# PCB10_1_PRABHU.net
KiCad netlist of a schematic drawn in EasyEDA
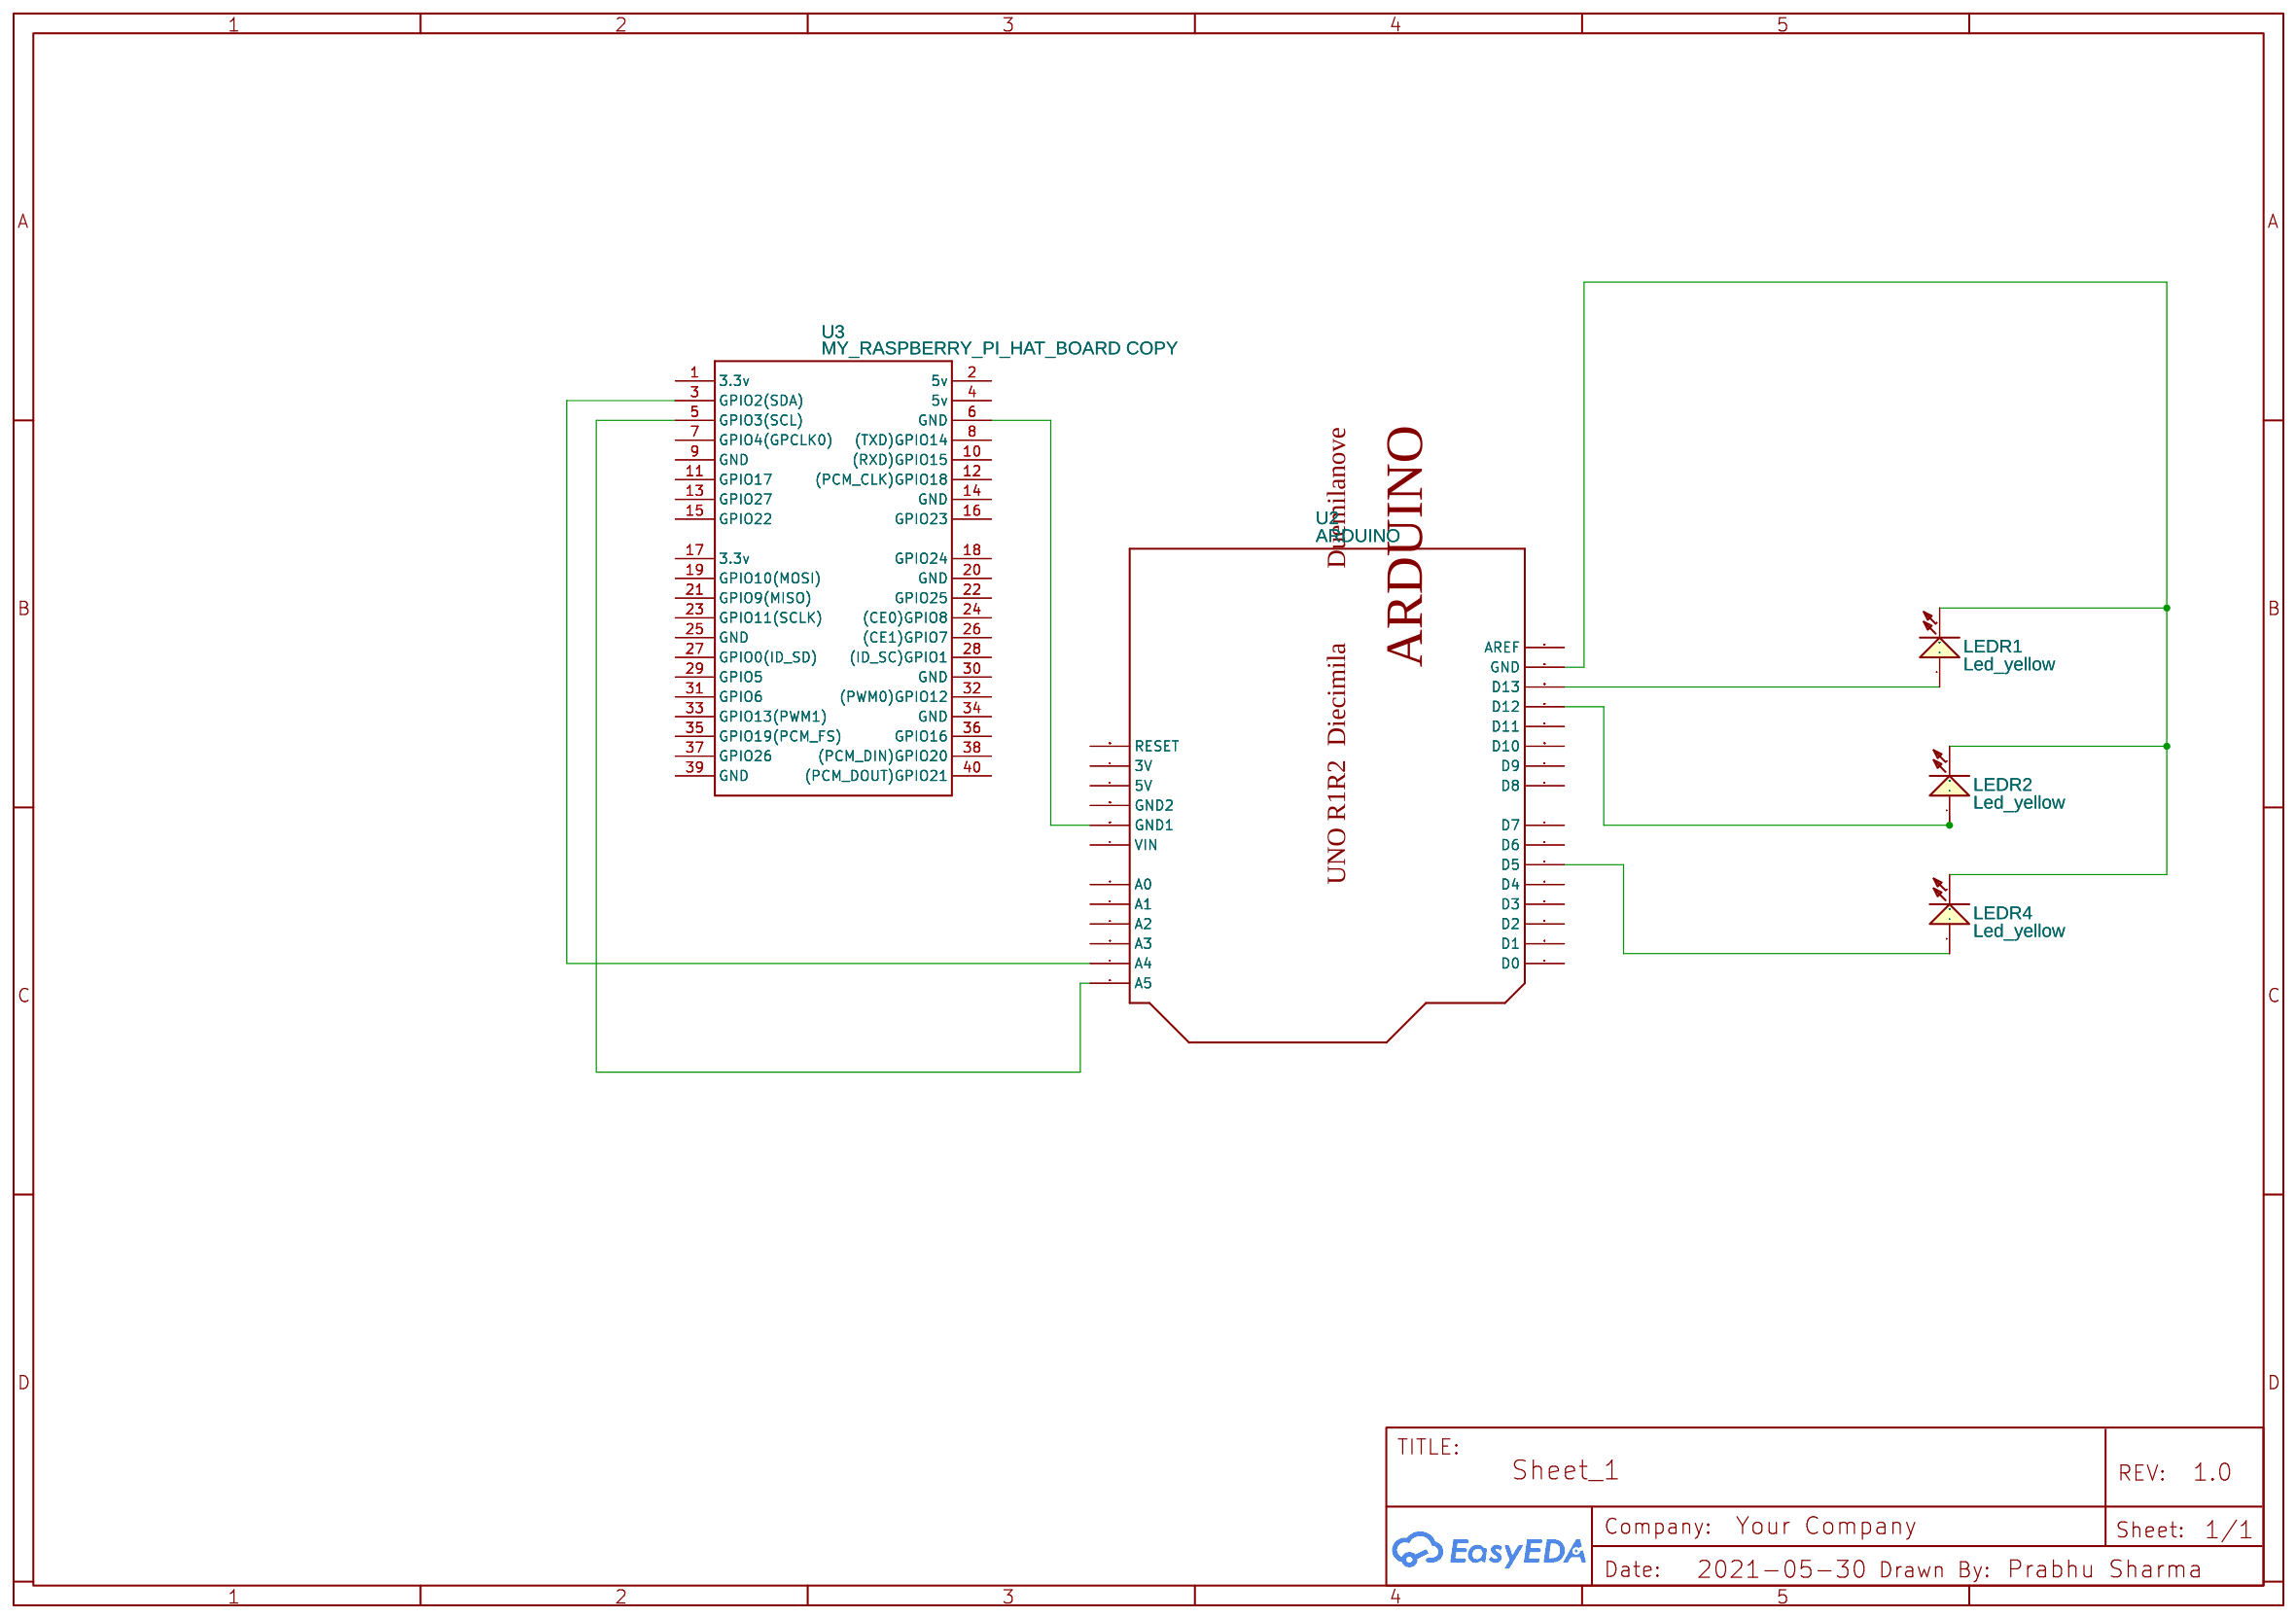
[diagram p0: schematic sheet]

(export (version "E")
  (design (tool "Eeschema 10.0.6"))
  (components
    (comp (ref "LEDR1") (value "Led_yellow") (libsource (lib "") (part "Led_r")))
    (comp (ref "LEDR2") (value "Led_yellow") (libsource (lib "") (part "Led_r")))
    (comp (ref "LEDR4") (value "Led_yellow") (libsource (lib "") (part "Led_r")))
    (comp (ref "U2") (value "ARDUINO") (libsource (lib "") (part "ARDUINO")))
    (comp (ref "U3")
      (value "MY_RASPBERRY_PI_HAT_BOARD COPY")
      (fields (field (name "BOM_Manufacturer Part") "Raspberry-Pi-3B-Plus-HAT-Board"))
      (libsource (lib "") (part "MY_RASPBERRY_PI_HAT_BOARD COPY"))
    )
  )
  (nets
    (net (code "1") (name "Net-(LEDR1-A)") (class "Default")
      (node (ref "LEDR1") (pin "1") (pinfunction "A_1") (pintype "input"))
      (node (ref "U2") (pin "D13") (pinfunction "D13_D13") (pintype "unspecified"))
    )
    (net (code "2") (name "Net-(LEDR1-C)") (class "Default")
      (node (ref "LEDR1") (pin "2") (pinfunction "C_2") (pintype "input"))
      (node (ref "LEDR2") (pin "2") (pinfunction "C_2") (pintype "input"))
      (node (ref "LEDR4") (pin "2") (pinfunction "C_2") (pintype "input"))
      (node (ref "U2") (pin "GND") (pinfunction "GND_GND") (pintype "passive"))
    )
    (net (code "3") (name "Net-(LEDR2-A)") (class "Default")
      (node (ref "LEDR2") (pin "1") (pinfunction "A_1") (pintype "input"))
      (node (ref "U2") (pin "D12") (pinfunction "D12_D12") (pintype "unspecified"))
    )
    (net (code "4") (name "Net-(LEDR4-A)") (class "Default")
      (node (ref "LEDR4") (pin "1") (pinfunction "A_1") (pintype "input"))
      (node (ref "U2") (pin "D5") (pinfunction "D5_D5") (pintype "unspecified"))
    )
    (net (code "5") (name "Net-(U2-PadGND1)") (class "Default")
      (node (ref "U2") (pin "GND1") (pinfunction "GND1_GND1") (pintype "passive"))
      (node (ref "U3") (pin "6") (pinfunction "GND_6") (pintype "bidirectional"))
    )
    (net (code "6") (name "Net-(U3-GPIO2(SDA))") (class "Default")
      (node (ref "U2") (pin "A4") (pinfunction "A4_A4") (pintype "unspecified"))
      (node (ref "U3") (pin "3") (pinfunction "GPIO2(SDA)_3") (pintype "bidirectional"))
    )
    (net (code "7") (name "Net-(U3-GPIO3(SCL))") (class "Default")
      (node (ref "U2") (pin "A5") (pinfunction "A5_A5") (pintype "unspecified"))
      (node (ref "U3") (pin "5") (pinfunction "GPIO3(SCL)_5") (pintype "bidirectional"))
    )
    (net (code "8") (name "unconnected-(U2-Pad3V)") (class "Default")
      (node (ref "U2") (pin "3V") (pinfunction "3V_3V") (pintype "passive"))
    )
    (net (code "9") (name "unconnected-(U2-Pad5V)") (class "Default")
      (node (ref "U2") (pin "5V") (pinfunction "5V_5V") (pintype "passive"))
    )
    (net (code "10") (name "unconnected-(U2-PadA0)") (class "Default")
      (node (ref "U2") (pin "A0") (pinfunction "A0_A0") (pintype "unspecified"))
    )
    (net (code "11") (name "unconnected-(U2-PadA1)") (class "Default")
      (node (ref "U2") (pin "A1") (pinfunction "A1_A1") (pintype "unspecified"))
    )
    (net (code "12") (name "unconnected-(U2-PadA2)") (class "Default")
      (node (ref "U2") (pin "A2") (pinfunction "A2_A2") (pintype "unspecified"))
    )
    (net (code "13") (name "unconnected-(U2-PadA3)") (class "Default")
      (node (ref "U2") (pin "A3") (pinfunction "A3_A3") (pintype "unspecified"))
    )
    (net (code "14") (name "unconnected-(U2-PadAREF)") (class "Default")
      (node (ref "U2") (pin "AREF") (pinfunction "AREF_AREF") (pintype "unspecified"))
    )
    (net (code "15") (name "unconnected-(U2-PadD0)") (class "Default")
      (node (ref "U2") (pin "D0") (pinfunction "D0_D0") (pintype "unspecified"))
    )
    (net (code "16") (name "unconnected-(U2-PadD1)") (class "Default")
      (node (ref "U2") (pin "D1") (pinfunction "D1_D1") (pintype "unspecified"))
    )
    (net (code "17") (name "unconnected-(U2-PadD2)") (class "Default")
      (node (ref "U2") (pin "D2") (pinfunction "D2_D2") (pintype "unspecified"))
    )
    (net (code "18") (name "unconnected-(U2-PadD3)") (class "Default")
      (node (ref "U2") (pin "D3") (pinfunction "D3_D3") (pintype "unspecified"))
    )
    (net (code "19") (name "unconnected-(U2-PadD4)") (class "Default")
      (node (ref "U2") (pin "D4") (pinfunction "D4_D4") (pintype "unspecified"))
    )
    (net (code "20") (name "unconnected-(U2-PadD6)") (class "Default")
      (node (ref "U2") (pin "D6") (pinfunction "D6_D6") (pintype "unspecified"))
    )
    (net (code "21") (name "unconnected-(U2-PadD7)") (class "Default")
      (node (ref "U2") (pin "D7") (pinfunction "D7_D7") (pintype "unspecified"))
    )
    (net (code "22") (name "unconnected-(U2-PadD8)") (class "Default")
      (node (ref "U2") (pin "D8") (pinfunction "D8_D8") (pintype "unspecified"))
    )
    (net (code "23") (name "unconnected-(U2-PadD9)") (class "Default")
      (node (ref "U2") (pin "D9") (pinfunction "D9_D9") (pintype "unspecified"))
    )
    (net (code "24") (name "unconnected-(U2-PadD10)") (class "Default")
      (node (ref "U2") (pin "D10") (pinfunction "D10_D10") (pintype "unspecified"))
    )
    (net (code "25") (name "unconnected-(U2-PadD11)") (class "Default")
      (node (ref "U2") (pin "D11") (pinfunction "D11_D11") (pintype "unspecified"))
    )
    (net (code "26") (name "unconnected-(U2-PadGND2)") (class "Default")
      (node (ref "U2") (pin "GND2") (pinfunction "GND2_GND2") (pintype "passive"))
    )
    (net (code "27") (name "unconnected-(U2-PadRESET)") (class "Default")
      (node (ref "U2") (pin "RESET") (pinfunction "RESET_RESET") (pintype "unspecified"))
    )
    (net (code "28") (name "unconnected-(U2-PadVIN)") (class "Default")
      (node (ref "U2") (pin "VIN") (pinfunction "VIN_VIN") (pintype "passive"))
    )
    (net (code "29") (name "unconnected-(U3-(CE0)GPIO8-Pad24)") (class "Default")
      (node (ref "U3") (pin "24") (pinfunction "(CE0)GPIO8_24") (pintype "bidirectional"))
    )
    (net (code "30") (name "unconnected-(U3-(CE1)GPIO7-Pad26)") (class "Default")
      (node (ref "U3") (pin "26") (pinfunction "(CE1)GPIO7_26") (pintype "bidirectional"))
    )
    (net (code "31") (name "unconnected-(U3-(ID_SC)GPIO1-Pad28)") (class "Default")
      (node (ref "U3") (pin "28") (pinfunction "(ID_SC)GPIO1_28") (pintype "bidirectional"))
    )
    (net (code "32") (name "unconnected-(U3-(PCM_CLK)GPIO18-Pad12)") (class "Default")
      (node (ref "U3") (pin "12") (pinfunction "(PCM_CLK)GPIO18_12") (pintype "bidirectional"))
    )
    (net (code "33") (name "unconnected-(U3-(PCM_DIN)GPIO20-Pad38)") (class "Default")
      (node (ref "U3") (pin "38") (pinfunction "(PCM_DIN)GPIO20_38") (pintype "bidirectional"))
    )
    (net (code "34") (name "unconnected-(U3-(PCM_DOUT)GPIO21-Pad40)") (class "Default")
      (node (ref "U3") (pin "40") (pinfunction "(PCM_DOUT)GPIO21_40") (pintype "bidirectional"))
    )
    (net (code "35") (name "unconnected-(U3-(PWM0)GPIO12-Pad32)") (class "Default")
      (node (ref "U3") (pin "32") (pinfunction "(PWM0)GPIO12_32") (pintype "bidirectional"))
    )
    (net (code "36") (name "unconnected-(U3-(RXD)GPIO15-Pad10)") (class "Default")
      (node (ref "U3") (pin "10") (pinfunction "(RXD)GPIO15_10") (pintype "bidirectional"))
    )
    (net (code "37") (name "unconnected-(U3-(TXD)GPIO14-Pad8)") (class "Default")
      (node (ref "U3") (pin "8") (pinfunction "(TXD)GPIO14_8") (pintype "bidirectional"))
    )
    (net (code "38") (name "unconnected-(U3-3.3v-Pad1)") (class "Default")
      (node (ref "U3") (pin "1") (pinfunction "3.3v_1") (pintype "bidirectional"))
    )
    (net (code "39") (name "unconnected-(U3-3.3v-Pad17)") (class "Default")
      (node (ref "U3") (pin "17") (pinfunction "3.3v_17") (pintype "bidirectional"))
    )
    (net (code "40") (name "unconnected-(U3-5v-Pad2)") (class "Default")
      (node (ref "U3") (pin "2") (pinfunction "5v_2") (pintype "bidirectional"))
    )
    (net (code "41") (name "unconnected-(U3-5v-Pad4)") (class "Default")
      (node (ref "U3") (pin "4") (pinfunction "5v_4") (pintype "bidirectional"))
    )
    (net (code "42") (name "unconnected-(U3-GND-Pad9)") (class "Default")
      (node (ref "U3") (pin "9") (pinfunction "GND_9") (pintype "bidirectional"))
    )
    (net (code "43") (name "unconnected-(U3-GND-Pad14)") (class "Default")
      (node (ref "U3") (pin "14") (pinfunction "GND_14") (pintype "bidirectional"))
    )
    (net (code "44") (name "unconnected-(U3-GND-Pad20)") (class "Default")
      (node (ref "U3") (pin "20") (pinfunction "GND_20") (pintype "bidirectional"))
    )
    (net (code "45") (name "unconnected-(U3-GND-Pad25)") (class "Default")
      (node (ref "U3") (pin "25") (pinfunction "GND_25") (pintype "bidirectional"))
    )
    (net (code "46") (name "unconnected-(U3-GND-Pad30)") (class "Default")
      (node (ref "U3") (pin "30") (pinfunction "GND_30") (pintype "bidirectional"))
    )
    (net (code "47") (name "unconnected-(U3-GND-Pad34)") (class "Default")
      (node (ref "U3") (pin "34") (pinfunction "GND_34") (pintype "bidirectional"))
    )
    (net (code "48") (name "unconnected-(U3-GND-Pad39)") (class "Default")
      (node (ref "U3") (pin "39") (pinfunction "GND_39") (pintype "bidirectional"))
    )
    (net (code "49") (name "unconnected-(U3-GPIO0(ID_SD)-Pad27)") (class "Default")
      (node (ref "U3") (pin "27") (pinfunction "GPIO0(ID_SD)_27") (pintype "bidirectional"))
    )
    (net (code "50") (name "unconnected-(U3-GPIO4(GPCLK0)-Pad7)") (class "Default")
      (node (ref "U3") (pin "7") (pinfunction "GPIO4(GPCLK0)_7") (pintype "bidirectional"))
    )
    (net (code "51") (name "unconnected-(U3-GPIO5-Pad29)") (class "Default")
      (node (ref "U3") (pin "29") (pinfunction "GPIO5_29") (pintype "bidirectional"))
    )
    (net (code "52") (name "unconnected-(U3-GPIO6-Pad31)") (class "Default")
      (node (ref "U3") (pin "31") (pinfunction "GPIO6_31") (pintype "bidirectional"))
    )
    (net (code "53") (name "unconnected-(U3-GPIO9(MISO)-Pad21)") (class "Default")
      (node (ref "U3") (pin "21") (pinfunction "GPIO9(MISO)_21") (pintype "bidirectional"))
    )
    (net (code "54") (name "unconnected-(U3-GPIO10(MOSI)-Pad19)") (class "Default")
      (node (ref "U3") (pin "19") (pinfunction "GPIO10(MOSI)_19") (pintype "bidirectional"))
    )
    (net (code "55") (name "unconnected-(U3-GPIO11(SCLK)-Pad23)") (class "Default")
      (node (ref "U3") (pin "23") (pinfunction "GPIO11(SCLK)_23") (pintype "bidirectional"))
    )
    (net (code "56") (name "unconnected-(U3-GPIO13(PWM1)-Pad33)") (class "Default")
      (node (ref "U3") (pin "33") (pinfunction "GPIO13(PWM1)_33") (pintype "bidirectional"))
    )
    (net (code "57") (name "unconnected-(U3-GPIO16-Pad36)") (class "Default")
      (node (ref "U3") (pin "36") (pinfunction "GPIO16_36") (pintype "bidirectional"))
    )
    (net (code "58") (name "unconnected-(U3-GPIO17-Pad11)") (class "Default")
      (node (ref "U3") (pin "11") (pinfunction "GPIO17_11") (pintype "bidirectional"))
    )
    (net (code "59") (name "unconnected-(U3-GPIO19(PCM_FS)-Pad35)") (class "Default")
      (node (ref "U3") (pin "35") (pinfunction "GPIO19(PCM_FS)_35") (pintype "bidirectional"))
    )
    (net (code "60") (name "unconnected-(U3-GPIO22-Pad15)") (class "Default")
      (node (ref "U3") (pin "15") (pinfunction "GPIO22_15") (pintype "bidirectional"))
    )
    (net (code "61") (name "unconnected-(U3-GPIO23-Pad16)") (class "Default")
      (node (ref "U3") (pin "16") (pinfunction "GPIO23_16") (pintype "bidirectional"))
    )
    (net (code "62") (name "unconnected-(U3-GPIO24-Pad18)") (class "Default")
      (node (ref "U3") (pin "18") (pinfunction "GPIO24_18") (pintype "bidirectional"))
    )
    (net (code "63") (name "unconnected-(U3-GPIO25-Pad22)") (class "Default")
      (node (ref "U3") (pin "22") (pinfunction "GPIO25_22") (pintype "bidirectional"))
    )
    (net (code "64") (name "unconnected-(U3-GPIO26-Pad37)") (class "Default")
      (node (ref "U3") (pin "37") (pinfunction "GPIO26_37") (pintype "bidirectional"))
    )
    (net (code "65") (name "unconnected-(U3-GPIO27-Pad13)") (class "Default")
      (node (ref "U3") (pin "13") (pinfunction "GPIO27_13") (pintype "bidirectional"))
    )
  )
)
